# dac-analog.net
KiCad netlist of a schematic drawn in Altium Designer
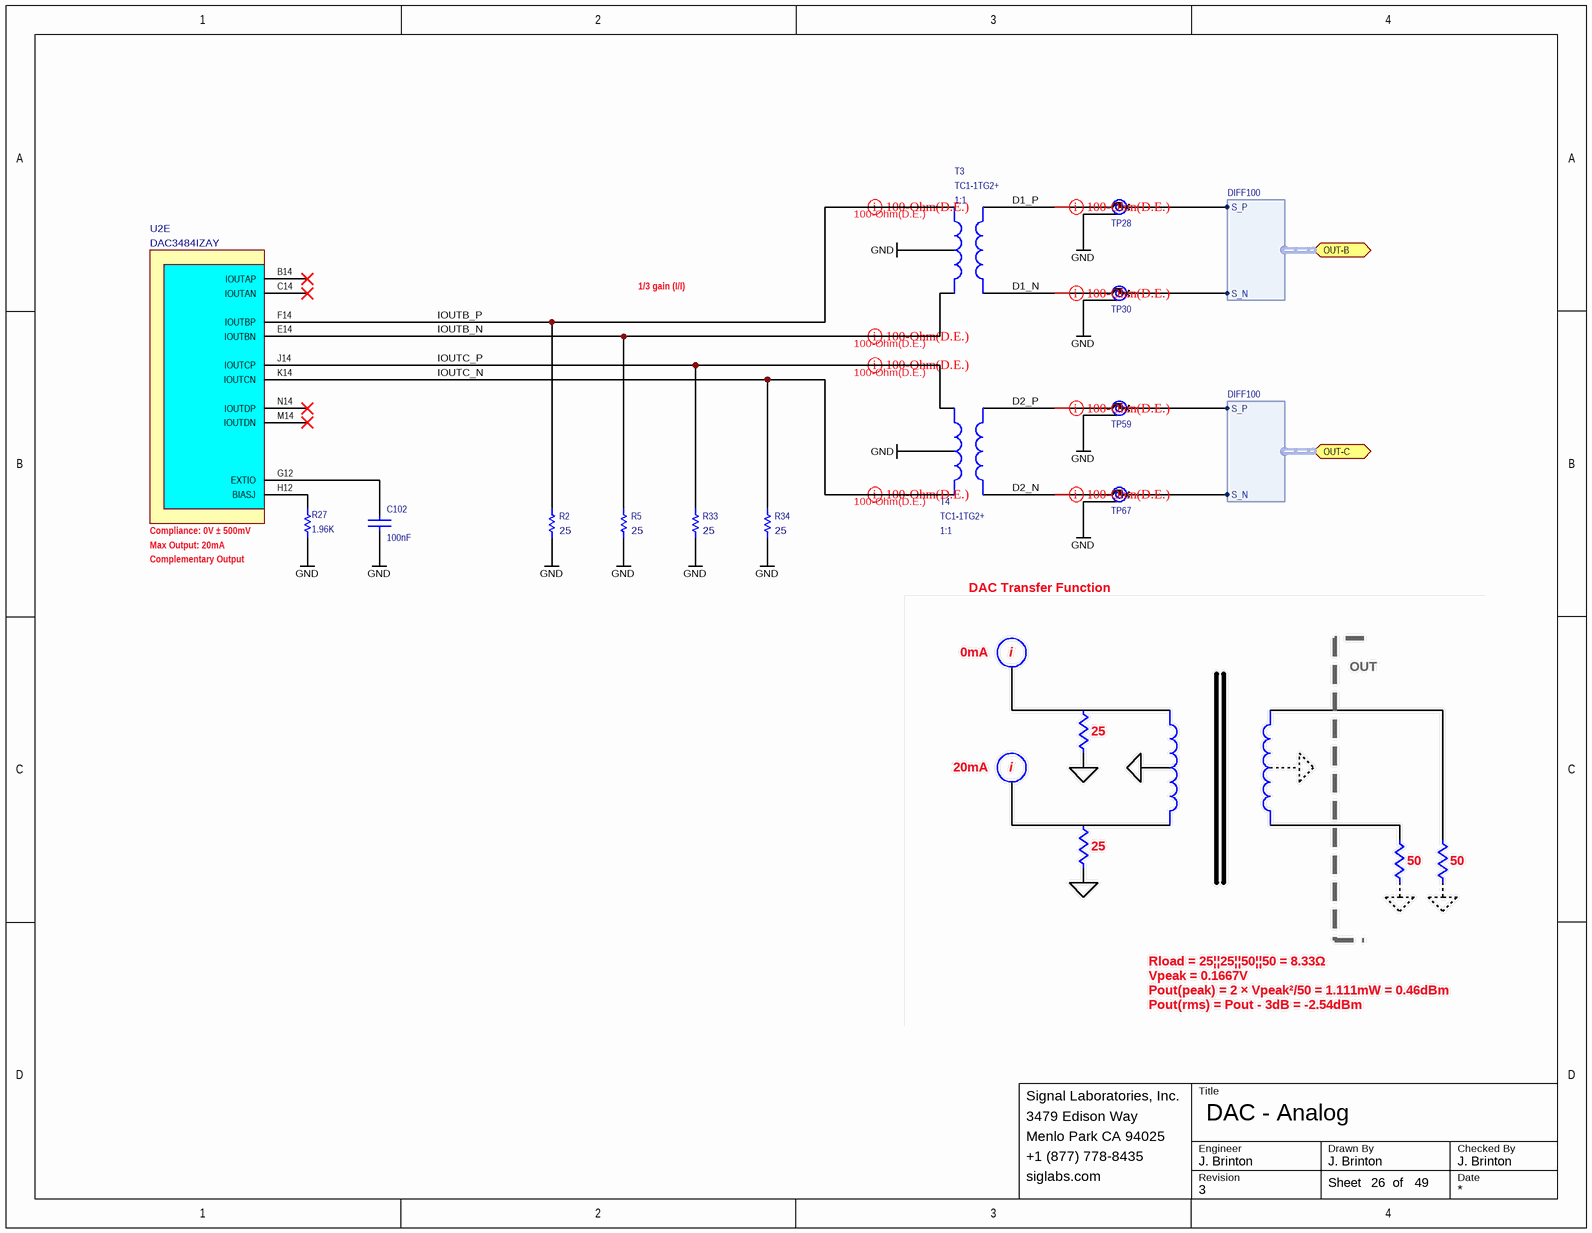
[diagram p0: dac-analog.SchDoc]

(export (version "E")
  (design (tool "Eeschema 10.0.6"))
  (components
    (comp (ref "C102")
      (value "100nF")
      (footprint "CAPC100X50X55L25N")
      (description "Ceramic Capacitor 100nF ±10% 16V X7R 0402")
      (fields (field (name "VOLTAGE") "16V") (field (name "MANUFACTURER") "Murata"))
      (libsource (lib "generic") (part "CAP 0402"))
    )
    (comp (ref "R2")
      (value "25")
      (footprint "generic:RESC1005X40N")
      (description "Thin Film Resistor 25 Ohm ±0.1% 0402")
      (fields (field (name "MANUFACTURER") "Vishay") (field (name "TOLERANCE") "±0.1%"))
      (libsource (lib "Graviton") (part "RES 0603"))
    )
    (comp (ref "R5")
      (value "25")
      (footprint "generic:RESC1005X40N")
      (description "Thin Film Resistor 25 Ohm ±0.1% 0402")
      (fields (field (name "MANUFACTURER") "Vishay") (field (name "TOLERANCE") "±0.1%"))
      (libsource (lib "Graviton") (part "RES 0603"))
    )
    (comp (ref "R27")
      (value "1.96K")
      (footprint "RESC1005X40N")
      (description "Thin Film Resistor 1.96k ±0.1% 0402")
      (fields (field (name "MANUFACTURER") "Panasonic") (field (name "TOLERANCE") "±0.1%"))
      (libsource (lib "Graviton") (part "RES 0402"))
    )
    (comp (ref "R33")
      (value "25")
      (footprint "generic:RESC1005X40N")
      (description "Thin Film Resistor 25 Ohm ±0.1% 0402")
      (fields (field (name "MANUFACTURER") "Vishay") (field (name "TOLERANCE") "±0.1%"))
      (libsource (lib "Graviton") (part "RES 0603"))
    )
    (comp (ref "R34")
      (value "25")
      (footprint "generic:RESC1005X40N")
      (description "Thin Film Resistor 25 Ohm ±0.1% 0402")
      (fields (field (name "MANUFACTURER") "Vishay") (field (name "TOLERANCE") "±0.1%"))
      (libsource (lib "Graviton") (part "RES 0603"))
    )
    (comp (ref "T3")
      (value "1:1")
      (footprint "AT224-1A")
      (description "RF Transformer 0.4 to 500MHz SMD")
      (fields
        (field (name "MANUFACTURER P/N") "TC1-1TG2+")
        (field (name "MANUFACTURER") "Mini-Circuits")
        (field (name "Comment") "TC1-1TG2+")
      )
      (libsource (lib "phase4") (part "TC1-1TG2+"))
    )
    (comp (ref "T4")
      (value "1:1")
      (footprint "AT224-1A")
      (description "RF Transformer 0.4 to 500MHz SMD")
      (fields
        (field (name "MANUFACTURER P/N") "TC1-1TG2+")
        (field (name "MANUFACTURER") "Mini-Circuits")
        (field (name "Comment") "TC1-1TG2+")
      )
      (libsource (lib "") (part "TC1-1TG2+_1"))
    )
    (comp (ref "TP28")
      (value "MS-180(20)")
      (footprint "MS-180(20)")
      (description "Coaxial Connector Switch")
      (fields (field (name "MANUFACTURER") "Hirose"))
      (libsource (lib "hirose") (part "MS-180(20)"))
    )
    (comp (ref "TP30")
      (value "MS-180(20)")
      (footprint "MS-180(20)")
      (description "Coaxial Connector Switch")
      (fields (field (name "MANUFACTURER") "Hirose"))
      (libsource (lib "hirose") (part "MS-180(20)"))
    )
    (comp (ref "TP59")
      (value "MS-180(20)")
      (footprint "MS-180(20)")
      (description "Coaxial Connector Switch")
      (fields (field (name "MANUFACTURER") "Hirose"))
      (libsource (lib "hirose") (part "MS-180(20)"))
    )
    (comp (ref "TP67")
      (value "MS-180(20)")
      (footprint "MS-180(20)")
      (description "Coaxial Connector Switch")
      (fields (field (name "MANUFACTURER") "Hirose"))
      (libsource (lib "hirose") (part "MS-180(20)"))
    )
    (comp (ref "U2")
      (value "DAC3484IZAY")
      (footprint "ZAY-BGA-196")
      (description "High Speed Quad DAC, 16-bit, 1.25GSPS")
      (fields (field (name "MANUFACTURER") "Texas Instruments"))
      (libsource (lib "ti") (part "DAC3484IZAY"))
    )
  )
  (nets
    (net (code "2") (name "/D1_N") (class "Default")
      (node (ref "T3") (pin "4") (pinfunction "Pri-_4") (pintype "passive"))
      (node (ref "TP30") (pin "A") (pinfunction "OUT_A") (pintype "passive"))
    )
    (net (code "3") (name "/D1_P") (class "Default")
      (node (ref "T3") (pin "6") (pinfunction "Pri+_6") (pintype "passive"))
      (node (ref "TP28") (pin "A") (pinfunction "OUT_A") (pintype "passive"))
    )
    (net (code "4") (name "/D2_N") (class "Default")
      (node (ref "T4") (pin "6") (pinfunction "Pri+_6") (pintype "passive"))
      (node (ref "TP67") (pin "A") (pinfunction "OUT_A") (pintype "passive"))
    )
    (net (code "5") (name "/D2_P") (class "Default")
      (node (ref "T4") (pin "4") (pinfunction "Pri-_4") (pintype "passive"))
      (node (ref "TP59") (pin "A") (pinfunction "OUT_A") (pintype "passive"))
    )
    (net (code "6") (name "/IOUTB_N") (class "Default")
      (node (ref "R5") (pin "2") (pinfunction "2_2") (pintype "passive"))
      (node (ref "T3") (pin "3") (pinfunction "Sec-_3") (pintype "passive"))
      (node (ref "U2") (pin "E14") (pinfunction "IOUTBN_E14") (pintype "passive"))
    )
    (net (code "7") (name "/IOUTB_P") (class "Default")
      (node (ref "R2") (pin "2") (pinfunction "2_2") (pintype "passive"))
      (node (ref "T3") (pin "1") (pinfunction "Sec+_1") (pintype "passive"))
      (node (ref "U2") (pin "F14") (pinfunction "IOUTBP_F14") (pintype "passive"))
    )
    (net (code "8") (name "/IOUTC_N") (class "Default")
      (node (ref "R34") (pin "2") (pinfunction "2_2") (pintype "passive"))
      (node (ref "T4") (pin "1") (pinfunction "Sec+_1") (pintype "passive"))
      (node (ref "U2") (pin "K14") (pinfunction "IOUTCN_K14") (pintype "passive"))
    )
    (net (code "9") (name "/IOUTC_P") (class "Default")
      (node (ref "R33") (pin "2") (pinfunction "2_2") (pintype "passive"))
      (node (ref "T4") (pin "3") (pinfunction "Sec-_3") (pintype "passive"))
      (node (ref "U2") (pin "J14") (pinfunction "IOUTCP_J14") (pintype "passive"))
    )
    (net (code "11") (name "GND") (class "Default")
      (node (ref "C102") (pin "1") (pinfunction "1_1") (pintype "passive"))
      (node (ref "R2") (pin "1") (pinfunction "1_1") (pintype "passive"))
      (node (ref "R27") (pin "1") (pinfunction "1_1") (pintype "passive"))
      (node (ref "R33") (pin "1") (pinfunction "1_1") (pintype "passive"))
      (node (ref "R34") (pin "1") (pinfunction "1_1") (pintype "passive"))
      (node (ref "R5") (pin "1") (pinfunction "1_1") (pintype "passive"))
      (node (ref "T3") (pin "2") (pinfunction "SecCT_2") (pintype "passive"))
      (node (ref "T4") (pin "2") (pinfunction "SecCT_2") (pintype "passive"))
      (node (ref "TP28") (pin "G") (pinfunction "GND_G") (pintype "passive"))
      (node (ref "TP30") (pin "G") (pinfunction "GND_G") (pintype "passive"))
      (node (ref "TP59") (pin "G") (pinfunction "GND_G") (pintype "passive"))
      (node (ref "TP67") (pin "G") (pinfunction "GND_G") (pintype "passive"))
    )
    (net (code "12") (name "Net-(U2E-BIASJ)") (class "Default")
      (node (ref "R27") (pin "2") (pinfunction "2_2") (pintype "passive"))
      (node (ref "U2") (pin "H12") (pinfunction "BIASJ_H12") (pintype "passive"))
    )
    (net (code "13") (name "Net-(U2E-EXTIO)") (class "Default")
      (node (ref "C102") (pin "2") (pinfunction "2_2") (pintype "passive"))
      (node (ref "U2") (pin "G12") (pinfunction "EXTIO_G12") (pintype "passive"))
    )
    (net (code "14") (name "unconnected-(TP28-IN-PadC)") (class "Default")
      (node (ref "TP28") (pin "C") (pinfunction "IN_C") (pintype "passive"))
    )
    (net (code "15") (name "unconnected-(TP30-IN-PadC)") (class "Default")
      (node (ref "TP30") (pin "C") (pinfunction "IN_C") (pintype "passive"))
    )
    (net (code "16") (name "unconnected-(TP59-IN-PadC)") (class "Default")
      (node (ref "TP59") (pin "C") (pinfunction "IN_C") (pintype "passive"))
    )
    (net (code "17") (name "unconnected-(TP67-IN-PadC)") (class "Default")
      (node (ref "TP67") (pin "C") (pinfunction "IN_C") (pintype "passive"))
    )
    (net (code "18") (name "unconnected-(U2E-IOUTAN-PadC14)") (class "Default")
      (node (ref "U2") (pin "C14") (pinfunction "IOUTAN_C14") (pintype "passive+no_connect"))
    )
    (net (code "19") (name "unconnected-(U2E-IOUTAP-PadB14)") (class "Default")
      (node (ref "U2") (pin "B14") (pinfunction "IOUTAP_B14") (pintype "passive+no_connect"))
    )
    (net (code "20") (name "unconnected-(U2E-IOUTDN-PadM14)") (class "Default")
      (node (ref "U2") (pin "M14") (pinfunction "IOUTDN_M14") (pintype "passive+no_connect"))
    )
    (net (code "21") (name "unconnected-(U2E-IOUTDP-PadN14)") (class "Default")
      (node (ref "U2") (pin "N14") (pinfunction "IOUTDP_N14") (pintype "passive+no_connect"))
    )
  )
)
